# M3_LPF.net
KiCad netlist of a schematic drawn in Altium Designer
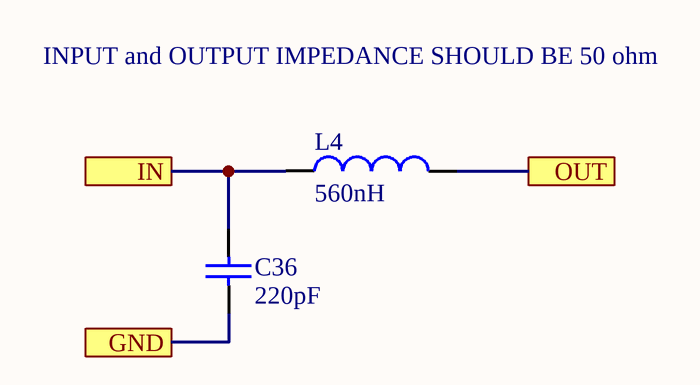
[diagram p0: M3_LPF.SchDoc]

(export (version "E")
  (design (tool "Eeschema 10.0.6"))
  (components
    (comp (ref "C36")
      (value "220pF")
      (footprint "SMD-0603")
      (description "Ceramic Capacitor 0603")
      (libsource (lib "LCR") (part "CAP0603"))
    )
    (comp (ref "L4")
      (value "560nH")
      (footprint "SMD-0603")
      (description "Inductor 0603")
      (libsource (lib "LCR") (part "L0603"))
    )
  )
  (nets
    (net (code "1") (name "/GND") (class "Default")
      (node (ref "C36") (pin "1") (pinfunction "1_1") (pintype "passive"))
    )
    (net (code "2") (name "/IN") (class "Default")
      (node (ref "C36") (pin "2") (pinfunction "2_2") (pintype "passive"))
      (node (ref "L4") (pin "1") (pinfunction "1_1") (pintype "passive"))
    )
    (net (code "3") (name "/OUT") (class "Default")
      (node (ref "L4") (pin "2") (pinfunction "2_2") (pintype "passive"))
    )
  )
)
